# 4xjacks_breakout.net
KiCad netlist of a schematic drawn in EAGLE
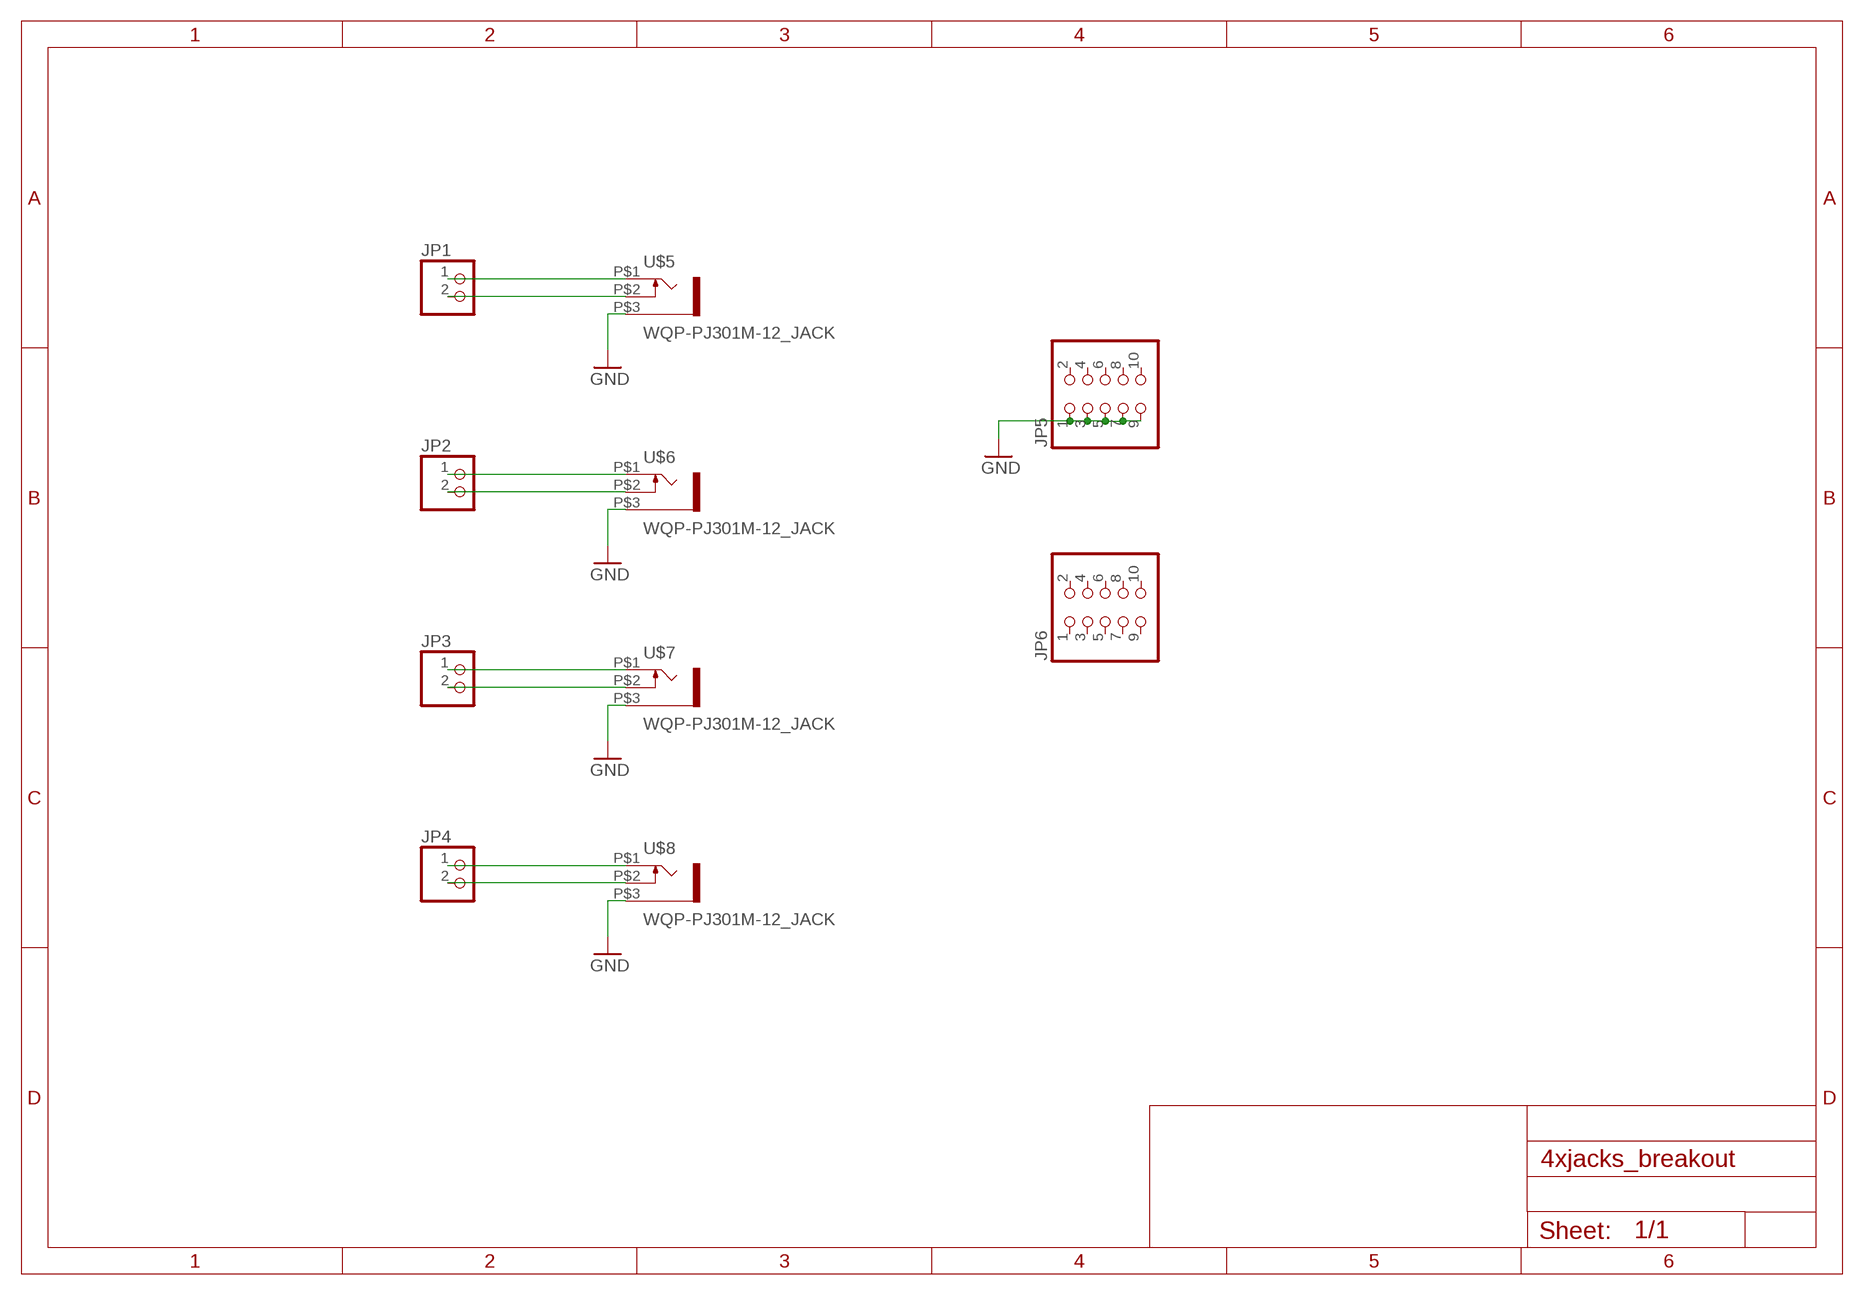
[diagram p0: schematic, sheet 1]

(export (version "E")
  (design (tool "Eeschema 10.0.6"))
  (components
    (comp (ref "JP1")
      (value "PINHD-1X2")
      (footprint "eagle-import:1X02")
      (libsource (lib "eagle-import") (part "PINHD-1X2"))
    )
    (comp (ref "JP2")
      (value "PINHD-1X2")
      (footprint "eagle-import:1X02")
      (libsource (lib "eagle-import") (part "PINHD-1X2"))
    )
    (comp (ref "JP3")
      (value "PINHD-1X2")
      (footprint "eagle-import:1X02")
      (libsource (lib "eagle-import") (part "PINHD-1X2"))
    )
    (comp (ref "JP4")
      (value "PINHD-1X2")
      (footprint "eagle-import:1X02")
      (libsource (lib "eagle-import") (part "PINHD-1X2"))
    )
    (comp (ref "JP5")
      (value "PINHD-2X5")
      (footprint "eagle-import:2X05")
      (libsource (lib "eagle-import") (part "PINHD-2X5"))
    )
    (comp (ref "JP6")
      (value "PINHD-2X5")
      (footprint "eagle-import:2X05")
      (libsource (lib "eagle-import") (part "PINHD-2X5"))
    )
    (comp (ref "U$5")
      (value "WQP-PJ301M-12_JACK")
      (footprint "eagle-import:WQP-PJ301M-12_JACK")
      (libsource (lib "eagle-import") (part "WQP-PJ301M-12_JACK"))
    )
    (comp (ref "U$6")
      (value "WQP-PJ301M-12_JACK")
      (footprint "eagle-import:WQP-PJ301M-12_JACK")
      (libsource (lib "eagle-import") (part "WQP-PJ301M-12_JACK"))
    )
    (comp (ref "U$7")
      (value "WQP-PJ301M-12_JACK")
      (footprint "eagle-import:WQP-PJ301M-12_JACK")
      (libsource (lib "eagle-import") (part "WQP-PJ301M-12_JACK"))
    )
    (comp (ref "U$8")
      (value "WQP-PJ301M-12_JACK")
      (footprint "eagle-import:WQP-PJ301M-12_JACK")
      (libsource (lib "eagle-import") (part "WQP-PJ301M-12_JACK"))
    )
  )
  (nets
    (net (code "1") (name "GND") (class "Default")
      (node (ref "JP5") (pin "1") (pinfunction "1_1") (pintype "passive"))
      (node (ref "JP5") (pin "3") (pinfunction "3_3") (pintype "passive"))
      (node (ref "JP5") (pin "5") (pinfunction "5_5") (pintype "passive"))
      (node (ref "JP5") (pin "7") (pinfunction "7_7") (pintype "passive"))
      (node (ref "JP5") (pin "9") (pinfunction "9_9") (pintype "passive"))
      (node (ref "U$5") (pin "P$3") (pinfunction "1_P$3") (pintype "passive"))
      (node (ref "U$6") (pin "P$3") (pinfunction "1_P$3") (pintype "passive"))
      (node (ref "U$7") (pin "P$3") (pinfunction "1_P$3") (pintype "passive"))
      (node (ref "U$8") (pin "P$3") (pinfunction "1_P$3") (pintype "passive"))
    )
    (net (code "2") (name "Net-(U$5-2)") (class "Default")
      (node (ref "JP1") (pin "1") (pinfunction "1_1") (pintype "passive"))
      (node (ref "U$5") (pin "P$1") (pinfunction "2_P$1") (pintype "passive"))
    )
    (net (code "3") (name "Net-(U$5-3)") (class "Default")
      (node (ref "JP1") (pin "2") (pinfunction "2_2") (pintype "passive"))
      (node (ref "U$5") (pin "P$2") (pinfunction "3_P$2") (pintype "passive"))
    )
    (net (code "4") (name "Net-(U$6-2)") (class "Default")
      (node (ref "JP2") (pin "1") (pinfunction "1_1") (pintype "passive"))
      (node (ref "U$6") (pin "P$1") (pinfunction "2_P$1") (pintype "passive"))
    )
    (net (code "5") (name "Net-(U$6-3)") (class "Default")
      (node (ref "JP2") (pin "2") (pinfunction "2_2") (pintype "passive"))
      (node (ref "U$6") (pin "P$2") (pinfunction "3_P$2") (pintype "passive"))
    )
    (net (code "6") (name "Net-(U$7-2)") (class "Default")
      (node (ref "JP3") (pin "1") (pinfunction "1_1") (pintype "passive"))
      (node (ref "U$7") (pin "P$1") (pinfunction "2_P$1") (pintype "passive"))
    )
    (net (code "7") (name "Net-(U$7-3)") (class "Default")
      (node (ref "JP3") (pin "2") (pinfunction "2_2") (pintype "passive"))
      (node (ref "U$7") (pin "P$2") (pinfunction "3_P$2") (pintype "passive"))
    )
    (net (code "8") (name "Net-(U$8-2)") (class "Default")
      (node (ref "JP4") (pin "1") (pinfunction "1_1") (pintype "passive"))
      (node (ref "U$8") (pin "P$1") (pinfunction "2_P$1") (pintype "passive"))
    )
    (net (code "9") (name "Net-(U$8-3)") (class "Default")
      (node (ref "JP4") (pin "2") (pinfunction "2_2") (pintype "passive"))
      (node (ref "U$8") (pin "P$2") (pinfunction "3_P$2") (pintype "passive"))
    )
    (net (code "10") (name "unconnected-(JP5-Pad2)") (class "Default")
      (node (ref "JP5") (pin "2") (pinfunction "2_2") (pintype "passive"))
    )
    (net (code "11") (name "unconnected-(JP5-Pad4)") (class "Default")
      (node (ref "JP5") (pin "4") (pinfunction "4_4") (pintype "passive"))
    )
    (net (code "12") (name "unconnected-(JP5-Pad6)") (class "Default")
      (node (ref "JP5") (pin "6") (pinfunction "6_6") (pintype "passive"))
    )
    (net (code "13") (name "unconnected-(JP5-Pad8)") (class "Default")
      (node (ref "JP5") (pin "8") (pinfunction "8_8") (pintype "passive"))
    )
    (net (code "14") (name "unconnected-(JP5-Pad10)") (class "Default")
      (node (ref "JP5") (pin "10") (pinfunction "10_10") (pintype "passive"))
    )
    (net (code "15") (name "unconnected-(JP6-Pad1)") (class "Default")
      (node (ref "JP6") (pin "1") (pinfunction "1_1") (pintype "passive"))
    )
    (net (code "16") (name "unconnected-(JP6-Pad2)") (class "Default")
      (node (ref "JP6") (pin "2") (pinfunction "2_2") (pintype "passive"))
    )
    (net (code "17") (name "unconnected-(JP6-Pad3)") (class "Default")
      (node (ref "JP6") (pin "3") (pinfunction "3_3") (pintype "passive"))
    )
    (net (code "18") (name "unconnected-(JP6-Pad4)") (class "Default")
      (node (ref "JP6") (pin "4") (pinfunction "4_4") (pintype "passive"))
    )
    (net (code "19") (name "unconnected-(JP6-Pad5)") (class "Default")
      (node (ref "JP6") (pin "5") (pinfunction "5_5") (pintype "passive"))
    )
    (net (code "20") (name "unconnected-(JP6-Pad6)") (class "Default")
      (node (ref "JP6") (pin "6") (pinfunction "6_6") (pintype "passive"))
    )
    (net (code "21") (name "unconnected-(JP6-Pad7)") (class "Default")
      (node (ref "JP6") (pin "7") (pinfunction "7_7") (pintype "passive"))
    )
    (net (code "22") (name "unconnected-(JP6-Pad8)") (class "Default")
      (node (ref "JP6") (pin "8") (pinfunction "8_8") (pintype "passive"))
    )
    (net (code "23") (name "unconnected-(JP6-Pad9)") (class "Default")
      (node (ref "JP6") (pin "9") (pinfunction "9_9") (pintype "passive"))
    )
    (net (code "24") (name "unconnected-(JP6-Pad10)") (class "Default")
      (node (ref "JP6") (pin "10") (pinfunction "10_10") (pintype "passive"))
    )
  )
)
